# Laser_Array_Temp_High_BRD_V1_1sch.net
KiCad netlist of a schematic drawn in EAGLE
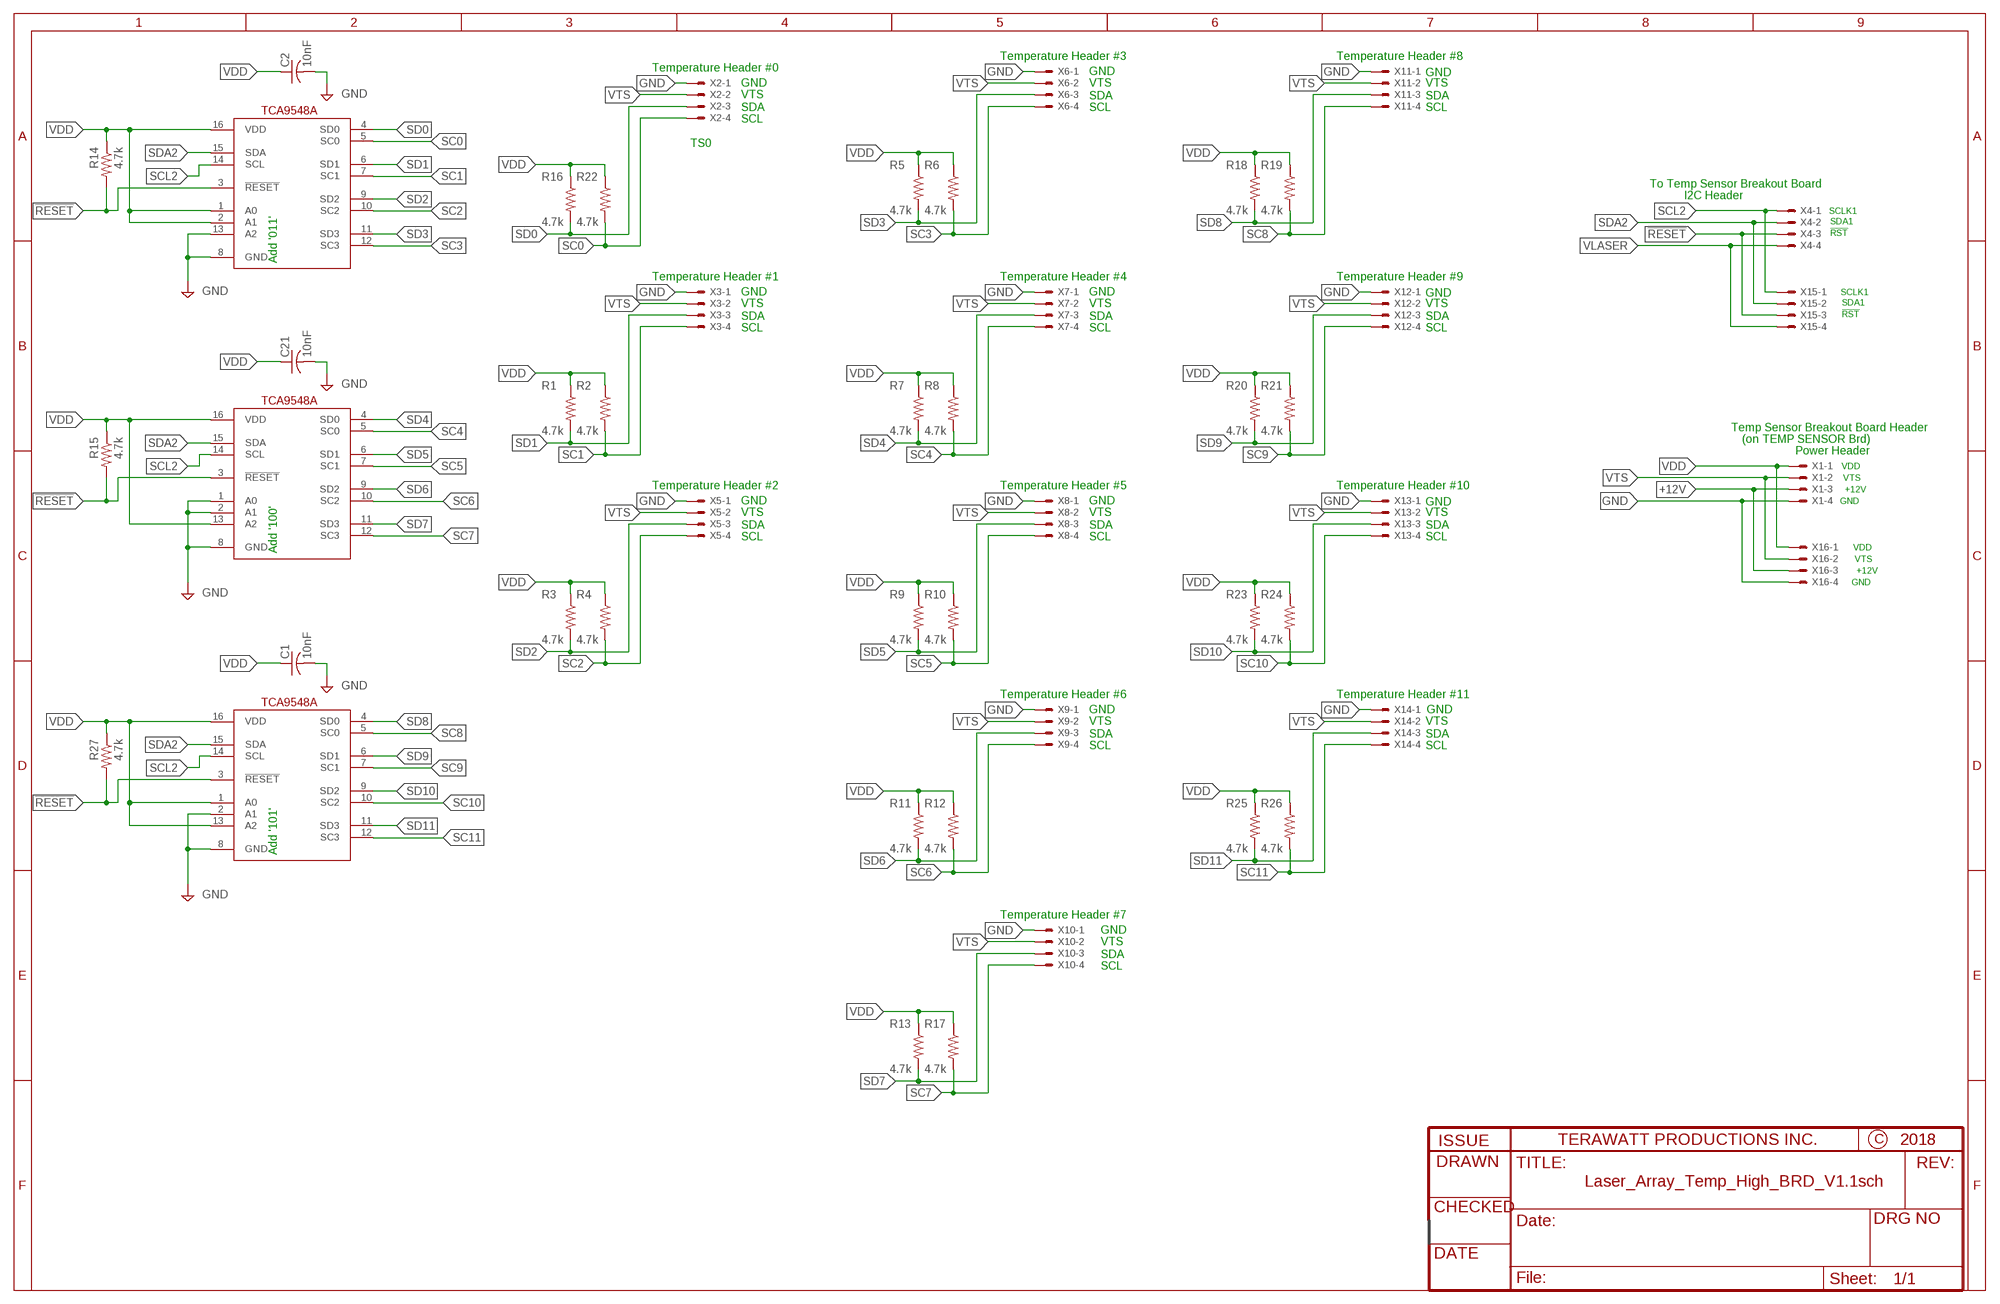
[diagram p0: schematic, sheet 1]

(export (version "E")
  (design (tool "Eeschema 10.0.6"))
  (components
    (comp (ref "C1")
      (value "10nF")
      (footprint "eagle-import:C0805")
      (libsource (lib "eagle-import") (part "C-USC0805"))
    )
    (comp (ref "C2")
      (value "10nF")
      (footprint "eagle-import:C0805")
      (libsource (lib "eagle-import") (part "C-USC0805"))
    )
    (comp (ref "C21")
      (value "10nF")
      (footprint "eagle-import:C0805")
      (libsource (lib "eagle-import") (part "C-USC0805"))
    )
    (comp (ref "R1")
      (value "4.7k")
      (footprint "eagle-import:M0805")
      (libsource (lib "eagle-import") (part "R-US_M0805"))
    )
    (comp (ref "R2")
      (value "4.7k")
      (footprint "eagle-import:M0805")
      (libsource (lib "eagle-import") (part "R-US_M0805"))
    )
    (comp (ref "R3")
      (value "4.7k")
      (footprint "eagle-import:M0805")
      (libsource (lib "eagle-import") (part "R-US_M0805"))
    )
    (comp (ref "R4")
      (value "4.7k")
      (footprint "eagle-import:M0805")
      (libsource (lib "eagle-import") (part "R-US_M0805"))
    )
    (comp (ref "R5")
      (value "4.7k")
      (footprint "eagle-import:M0805")
      (libsource (lib "eagle-import") (part "R-US_M0805"))
    )
    (comp (ref "R6")
      (value "4.7k")
      (footprint "eagle-import:M0805")
      (libsource (lib "eagle-import") (part "R-US_M0805"))
    )
    (comp (ref "R7")
      (value "4.7k")
      (footprint "eagle-import:M0805")
      (libsource (lib "eagle-import") (part "R-US_M0805"))
    )
    (comp (ref "R8")
      (value "4.7k")
      (footprint "eagle-import:M0805")
      (libsource (lib "eagle-import") (part "R-US_M0805"))
    )
    (comp (ref "R9")
      (value "4.7k")
      (footprint "eagle-import:M0805")
      (libsource (lib "eagle-import") (part "R-US_M0805"))
    )
    (comp (ref "R10")
      (value "4.7k")
      (footprint "eagle-import:M0805")
      (libsource (lib "eagle-import") (part "R-US_M0805"))
    )
    (comp (ref "R11")
      (value "4.7k")
      (footprint "eagle-import:M0805")
      (libsource (lib "eagle-import") (part "R-US_M0805"))
    )
    (comp (ref "R12")
      (value "4.7k")
      (footprint "eagle-import:M0805")
      (libsource (lib "eagle-import") (part "R-US_M0805"))
    )
    (comp (ref "R13")
      (value "4.7k")
      (footprint "eagle-import:M0805")
      (libsource (lib "eagle-import") (part "R-US_M0805"))
    )
    (comp (ref "R14")
      (value "4.7k")
      (footprint "eagle-import:M0805")
      (libsource (lib "eagle-import") (part "R-US_M0805"))
    )
    (comp (ref "R15")
      (value "4.7k")
      (footprint "eagle-import:M0805")
      (libsource (lib "eagle-import") (part "R-US_M0805"))
    )
    (comp (ref "R16")
      (value "4.7k")
      (footprint "eagle-import:M0805")
      (libsource (lib "eagle-import") (part "R-US_M0805"))
    )
    (comp (ref "R17")
      (value "4.7k")
      (footprint "eagle-import:M0805")
      (libsource (lib "eagle-import") (part "R-US_M0805"))
    )
    (comp (ref "R18")
      (value "4.7k")
      (footprint "eagle-import:M0805")
      (libsource (lib "eagle-import") (part "R-US_M0805"))
    )
    (comp (ref "R19")
      (value "4.7k")
      (footprint "eagle-import:M0805")
      (libsource (lib "eagle-import") (part "R-US_M0805"))
    )
    (comp (ref "R20")
      (value "4.7k")
      (footprint "eagle-import:M0805")
      (libsource (lib "eagle-import") (part "R-US_M0805"))
    )
    (comp (ref "R21")
      (value "4.7k")
      (footprint "eagle-import:M0805")
      (libsource (lib "eagle-import") (part "R-US_M0805"))
    )
    (comp (ref "R22")
      (value "4.7k")
      (footprint "eagle-import:M0805")
      (libsource (lib "eagle-import") (part "R-US_M0805"))
    )
    (comp (ref "R23")
      (value "4.7k")
      (footprint "eagle-import:M0805")
      (libsource (lib "eagle-import") (part "R-US_M0805"))
    )
    (comp (ref "R24")
      (value "4.7k")
      (footprint "eagle-import:M0805")
      (libsource (lib "eagle-import") (part "R-US_M0805"))
    )
    (comp (ref "R25")
      (value "4.7k")
      (footprint "eagle-import:M0805")
      (libsource (lib "eagle-import") (part "R-US_M0805"))
    )
    (comp (ref "R26")
      (value "4.7k")
      (footprint "eagle-import:M0805")
      (libsource (lib "eagle-import") (part "R-US_M0805"))
    )
    (comp (ref "R27")
      (value "4.7k")
      (footprint "eagle-import:M0805")
      (libsource (lib "eagle-import") (part "R-US_M0805"))
    )
    (comp (ref "U1")
      (value "TCA9546A")
      (footprint "eagle-import:SOIC16N")
      (libsource (lib "eagle-import") (part "TCA9546A"))
    )
    (comp (ref "U2")
      (value "TCA9546A")
      (footprint "eagle-import:SOIC16N")
      (libsource (lib "eagle-import") (part "TCA9546A"))
    )
    (comp (ref "U3")
      (value "TCA9546A")
      (footprint "eagle-import:SOIC16N")
      (libsource (lib "eagle-import") (part "TCA9546A"))
    )
    (comp (ref "X1")
      (value "22-23-2041")
      (footprint "eagle-import:22-23-2041")
      (fields (field (name "MF") "MOLEX"))
      (libsource (lib "eagle-import") (part "22-23-2041"))
    )
    (comp (ref "X2")
      (value "22-23-2041")
      (footprint "eagle-import:22-23-2041")
      (fields (field (name "MF") "MOLEX"))
      (libsource (lib "eagle-import") (part "22-23-2041"))
    )
    (comp (ref "X3")
      (value "22-23-2041")
      (footprint "eagle-import:22-23-2041")
      (fields (field (name "MF") "MOLEX"))
      (libsource (lib "eagle-import") (part "22-23-2041"))
    )
    (comp (ref "X4")
      (value "22-23-2041")
      (footprint "eagle-import:22-23-2041")
      (fields (field (name "MF") "MOLEX"))
      (libsource (lib "eagle-import") (part "22-23-2041"))
    )
    (comp (ref "X5")
      (value "22-23-2041")
      (footprint "eagle-import:22-23-2041")
      (fields (field (name "MF") "MOLEX"))
      (libsource (lib "eagle-import") (part "22-23-2041"))
    )
    (comp (ref "X6")
      (value "22-23-2041")
      (footprint "eagle-import:22-23-2041")
      (fields (field (name "MF") "MOLEX"))
      (libsource (lib "eagle-import") (part "22-23-2041"))
    )
    (comp (ref "X7")
      (value "22-23-2041")
      (footprint "eagle-import:22-23-2041")
      (fields (field (name "MF") "MOLEX"))
      (libsource (lib "eagle-import") (part "22-23-2041"))
    )
    (comp (ref "X8")
      (value "22-23-2041")
      (footprint "eagle-import:22-23-2041")
      (fields (field (name "MF") "MOLEX"))
      (libsource (lib "eagle-import") (part "22-23-2041"))
    )
    (comp (ref "X9")
      (value "22-23-2041")
      (footprint "eagle-import:22-23-2041")
      (fields (field (name "MF") "MOLEX"))
      (libsource (lib "eagle-import") (part "22-23-2041"))
    )
    (comp (ref "X10")
      (value "22-23-2041")
      (footprint "eagle-import:22-23-2041")
      (fields (field (name "MF") "MOLEX"))
      (libsource (lib "eagle-import") (part "22-23-2041"))
    )
    (comp (ref "X11")
      (value "22-23-2041")
      (footprint "eagle-import:22-23-2041")
      (fields (field (name "MF") "MOLEX"))
      (libsource (lib "eagle-import") (part "22-23-2041"))
    )
    (comp (ref "X12")
      (value "22-23-2041")
      (footprint "eagle-import:22-23-2041")
      (fields (field (name "MF") "MOLEX"))
      (libsource (lib "eagle-import") (part "22-23-2041"))
    )
    (comp (ref "X13")
      (value "22-23-2041")
      (footprint "eagle-import:22-23-2041")
      (fields (field (name "MF") "MOLEX"))
      (libsource (lib "eagle-import") (part "22-23-2041"))
    )
    (comp (ref "X14")
      (value "22-23-2041")
      (footprint "eagle-import:22-23-2041")
      (fields (field (name "MF") "MOLEX"))
      (libsource (lib "eagle-import") (part "22-23-2041"))
    )
    (comp (ref "X15")
      (value "22-23-2041")
      (footprint "eagle-import:22-23-2041")
      (fields (field (name "MF") "MOLEX"))
      (libsource (lib "eagle-import") (part "22-23-2041"))
    )
    (comp (ref "X16")
      (value "22-23-2041")
      (footprint "eagle-import:22-23-2041")
      (fields (field (name "MF") "MOLEX"))
      (libsource (lib "eagle-import") (part "22-23-2041"))
    )
  )
  (nets
    (net (code "1") (name "+12V") (class "Default")
      (node (ref "X1") (pin "3") (pinfunction "S_3") (pintype "passive"))
      (node (ref "X16") (pin "3") (pinfunction "S_3") (pintype "passive"))
    )
    (net (code "2") (name "/~{RESET}") (class "Default")
      (node (ref "R14") (pin "2") (pinfunction "2_2") (pintype "passive"))
      (node (ref "R15") (pin "2") (pinfunction "2_2") (pintype "passive"))
      (node (ref "R27") (pin "2") (pinfunction "2_2") (pintype "passive"))
      (node (ref "U1") (pin "3") (pinfunction "~{RESET}_3") (pintype "bidirectional"))
      (node (ref "U2") (pin "3") (pinfunction "~{RESET}_3") (pintype "bidirectional"))
      (node (ref "U3") (pin "3") (pinfunction "~{RESET}_3") (pintype "bidirectional"))
      (node (ref "X15") (pin "3") (pinfunction "S_3") (pintype "passive"))
      (node (ref "X4") (pin "3") (pinfunction "S_3") (pintype "passive"))
    )
    (net (code "3") (name "GND") (class "Default")
      (node (ref "C1") (pin "2") (pinfunction "2_2") (pintype "passive"))
      (node (ref "C2") (pin "2") (pinfunction "2_2") (pintype "passive"))
      (node (ref "C21") (pin "2") (pinfunction "2_2") (pintype "passive"))
      (node (ref "U1") (pin "13") (pinfunction "A2_13") (pintype "bidirectional"))
      (node (ref "U1") (pin "8") (pinfunction "GND_8") (pintype "bidirectional"))
      (node (ref "U2") (pin "1") (pinfunction "A0_1") (pintype "bidirectional"))
      (node (ref "U2") (pin "2") (pinfunction "A1_2") (pintype "bidirectional"))
      (node (ref "U2") (pin "8") (pinfunction "GND_8") (pintype "bidirectional"))
      (node (ref "U3") (pin "2") (pinfunction "A1_2") (pintype "bidirectional"))
      (node (ref "U3") (pin "8") (pinfunction "GND_8") (pintype "bidirectional"))
      (node (ref "X1") (pin "4") (pinfunction "S_4") (pintype "passive"))
      (node (ref "X10") (pin "1") (pinfunction "S_1") (pintype "passive"))
      (node (ref "X11") (pin "1") (pinfunction "S_1") (pintype "passive"))
      (node (ref "X12") (pin "1") (pinfunction "S_1") (pintype "passive"))
      (node (ref "X13") (pin "1") (pinfunction "S_1") (pintype "passive"))
      (node (ref "X14") (pin "1") (pinfunction "S_1") (pintype "passive"))
      (node (ref "X16") (pin "4") (pinfunction "S_4") (pintype "passive"))
      (node (ref "X2") (pin "1") (pinfunction "S_1") (pintype "passive"))
      (node (ref "X3") (pin "1") (pinfunction "S_1") (pintype "passive"))
      (node (ref "X5") (pin "1") (pinfunction "S_1") (pintype "passive"))
      (node (ref "X6") (pin "1") (pinfunction "S_1") (pintype "passive"))
      (node (ref "X7") (pin "1") (pinfunction "S_1") (pintype "passive"))
      (node (ref "X8") (pin "1") (pinfunction "S_1") (pintype "passive"))
      (node (ref "X9") (pin "1") (pinfunction "S_1") (pintype "passive"))
    )
    (net (code "4") (name "SC0") (class "Default")
      (node (ref "R22") (pin "2") (pinfunction "2_2") (pintype "passive"))
      (node (ref "U1") (pin "5") (pinfunction "SC0_5") (pintype "bidirectional"))
      (node (ref "X2") (pin "4") (pinfunction "S_4") (pintype "passive"))
    )
    (net (code "5") (name "SC1") (class "Default")
      (node (ref "R2") (pin "2") (pinfunction "2_2") (pintype "passive"))
      (node (ref "U1") (pin "7") (pinfunction "SC1_7") (pintype "bidirectional"))
      (node (ref "X3") (pin "4") (pinfunction "S_4") (pintype "passive"))
    )
    (net (code "6") (name "SC2") (class "Default")
      (node (ref "R4") (pin "2") (pinfunction "2_2") (pintype "passive"))
      (node (ref "U1") (pin "10") (pinfunction "SC2_10") (pintype "bidirectional"))
      (node (ref "X5") (pin "4") (pinfunction "S_4") (pintype "passive"))
    )
    (net (code "7") (name "SC3") (class "Default")
      (node (ref "R6") (pin "2") (pinfunction "2_2") (pintype "passive"))
      (node (ref "U1") (pin "12") (pinfunction "SC3_12") (pintype "bidirectional"))
      (node (ref "X6") (pin "4") (pinfunction "S_4") (pintype "passive"))
    )
    (net (code "8") (name "SC4") (class "Default")
      (node (ref "R8") (pin "2") (pinfunction "2_2") (pintype "passive"))
      (node (ref "U2") (pin "5") (pinfunction "SC0_5") (pintype "bidirectional"))
      (node (ref "X7") (pin "4") (pinfunction "S_4") (pintype "passive"))
    )
    (net (code "9") (name "SC5") (class "Default")
      (node (ref "R10") (pin "2") (pinfunction "2_2") (pintype "passive"))
      (node (ref "U2") (pin "7") (pinfunction "SC1_7") (pintype "bidirectional"))
      (node (ref "X8") (pin "4") (pinfunction "S_4") (pintype "passive"))
    )
    (net (code "10") (name "SC6") (class "Default")
      (node (ref "R12") (pin "2") (pinfunction "2_2") (pintype "passive"))
      (node (ref "U2") (pin "10") (pinfunction "SC2_10") (pintype "bidirectional"))
      (node (ref "X9") (pin "4") (pinfunction "S_4") (pintype "passive"))
    )
    (net (code "11") (name "SC7") (class "Default")
      (node (ref "R17") (pin "2") (pinfunction "2_2") (pintype "passive"))
      (node (ref "U2") (pin "12") (pinfunction "SC3_12") (pintype "bidirectional"))
      (node (ref "X10") (pin "4") (pinfunction "S_4") (pintype "passive"))
    )
    (net (code "12") (name "SC8") (class "Default")
      (node (ref "R19") (pin "2") (pinfunction "2_2") (pintype "passive"))
      (node (ref "U3") (pin "5") (pinfunction "SC0_5") (pintype "bidirectional"))
      (node (ref "X11") (pin "4") (pinfunction "S_4") (pintype "passive"))
    )
    (net (code "13") (name "SC9") (class "Default")
      (node (ref "R21") (pin "2") (pinfunction "2_2") (pintype "passive"))
      (node (ref "U3") (pin "7") (pinfunction "SC1_7") (pintype "bidirectional"))
      (node (ref "X12") (pin "4") (pinfunction "S_4") (pintype "passive"))
    )
    (net (code "14") (name "SC10") (class "Default")
      (node (ref "R24") (pin "2") (pinfunction "2_2") (pintype "passive"))
      (node (ref "U3") (pin "10") (pinfunction "SC2_10") (pintype "bidirectional"))
      (node (ref "X13") (pin "4") (pinfunction "S_4") (pintype "passive"))
    )
    (net (code "15") (name "SC11") (class "Default")
      (node (ref "R26") (pin "2") (pinfunction "2_2") (pintype "passive"))
      (node (ref "U3") (pin "12") (pinfunction "SC3_12") (pintype "bidirectional"))
      (node (ref "X14") (pin "4") (pinfunction "S_4") (pintype "passive"))
    )
    (net (code "16") (name "SCL2") (class "Default")
      (node (ref "U1") (pin "14") (pinfunction "SCL_14") (pintype "bidirectional"))
      (node (ref "U2") (pin "14") (pinfunction "SCL_14") (pintype "bidirectional"))
      (node (ref "U3") (pin "14") (pinfunction "SCL_14") (pintype "bidirectional"))
      (node (ref "X15") (pin "1") (pinfunction "S_1") (pintype "passive"))
      (node (ref "X4") (pin "1") (pinfunction "S_1") (pintype "passive"))
    )
    (net (code "17") (name "SD0") (class "Default")
      (node (ref "R16") (pin "2") (pinfunction "2_2") (pintype "passive"))
      (node (ref "U1") (pin "4") (pinfunction "SD0_4") (pintype "bidirectional"))
      (node (ref "X2") (pin "3") (pinfunction "S_3") (pintype "passive"))
    )
    (net (code "18") (name "SD1") (class "Default")
      (node (ref "R1") (pin "2") (pinfunction "2_2") (pintype "passive"))
      (node (ref "U1") (pin "6") (pinfunction "SD1_6") (pintype "bidirectional"))
      (node (ref "X3") (pin "3") (pinfunction "S_3") (pintype "passive"))
    )
    (net (code "19") (name "SD2") (class "Default")
      (node (ref "R3") (pin "2") (pinfunction "2_2") (pintype "passive"))
      (node (ref "U1") (pin "9") (pinfunction "SD2_9") (pintype "bidirectional"))
      (node (ref "X5") (pin "3") (pinfunction "S_3") (pintype "passive"))
    )
    (net (code "20") (name "SD3") (class "Default")
      (node (ref "R5") (pin "2") (pinfunction "2_2") (pintype "passive"))
      (node (ref "U1") (pin "11") (pinfunction "SD3_11") (pintype "bidirectional"))
      (node (ref "X6") (pin "3") (pinfunction "S_3") (pintype "passive"))
    )
    (net (code "21") (name "SD4") (class "Default")
      (node (ref "R7") (pin "2") (pinfunction "2_2") (pintype "passive"))
      (node (ref "U2") (pin "4") (pinfunction "SD0_4") (pintype "bidirectional"))
      (node (ref "X7") (pin "3") (pinfunction "S_3") (pintype "passive"))
    )
    (net (code "22") (name "SD5") (class "Default")
      (node (ref "R9") (pin "2") (pinfunction "2_2") (pintype "passive"))
      (node (ref "U2") (pin "6") (pinfunction "SD1_6") (pintype "bidirectional"))
      (node (ref "X8") (pin "3") (pinfunction "S_3") (pintype "passive"))
    )
    (net (code "23") (name "SD6") (class "Default")
      (node (ref "R11") (pin "2") (pinfunction "2_2") (pintype "passive"))
      (node (ref "U2") (pin "9") (pinfunction "SD2_9") (pintype "bidirectional"))
      (node (ref "X9") (pin "3") (pinfunction "S_3") (pintype "passive"))
    )
    (net (code "24") (name "SD7") (class "Default")
      (node (ref "R13") (pin "2") (pinfunction "2_2") (pintype "passive"))
      (node (ref "U2") (pin "11") (pinfunction "SD3_11") (pintype "bidirectional"))
      (node (ref "X10") (pin "3") (pinfunction "S_3") (pintype "passive"))
    )
    (net (code "25") (name "SD8") (class "Default")
      (node (ref "R18") (pin "2") (pinfunction "2_2") (pintype "passive"))
      (node (ref "U3") (pin "4") (pinfunction "SD0_4") (pintype "bidirectional"))
      (node (ref "X11") (pin "3") (pinfunction "S_3") (pintype "passive"))
    )
    (net (code "26") (name "SD9") (class "Default")
      (node (ref "R20") (pin "2") (pinfunction "2_2") (pintype "passive"))
      (node (ref "U3") (pin "6") (pinfunction "SD1_6") (pintype "bidirectional"))
      (node (ref "X12") (pin "3") (pinfunction "S_3") (pintype "passive"))
    )
    (net (code "27") (name "SD10") (class "Default")
      (node (ref "R23") (pin "2") (pinfunction "2_2") (pintype "passive"))
      (node (ref "U3") (pin "9") (pinfunction "SD2_9") (pintype "bidirectional"))
      (node (ref "X13") (pin "3") (pinfunction "S_3") (pintype "passive"))
    )
    (net (code "28") (name "SD11") (class "Default")
      (node (ref "R25") (pin "2") (pinfunction "2_2") (pintype "passive"))
      (node (ref "U3") (pin "11") (pinfunction "SD3_11") (pintype "bidirectional"))
      (node (ref "X14") (pin "3") (pinfunction "S_3") (pintype "passive"))
    )
    (net (code "29") (name "SDA2") (class "Default")
      (node (ref "U1") (pin "15") (pinfunction "SDA_15") (pintype "bidirectional"))
      (node (ref "U2") (pin "15") (pinfunction "SDA_15") (pintype "bidirectional"))
      (node (ref "U3") (pin "15") (pinfunction "SDA_15") (pintype "bidirectional"))
      (node (ref "X15") (pin "2") (pinfunction "S_2") (pintype "passive"))
      (node (ref "X4") (pin "2") (pinfunction "S_2") (pintype "passive"))
    )
    (net (code "30") (name "VDD") (class "Default")
      (node (ref "C1") (pin "1") (pinfunction "1_1") (pintype "passive"))
      (node (ref "C2") (pin "1") (pinfunction "1_1") (pintype "passive"))
      (node (ref "C21") (pin "1") (pinfunction "1_1") (pintype "passive"))
      (node (ref "R1") (pin "1") (pinfunction "1_1") (pintype "passive"))
      (node (ref "R10") (pin "1") (pinfunction "1_1") (pintype "passive"))
      (node (ref "R11") (pin "1") (pinfunction "1_1") (pintype "passive"))
      (node (ref "R12") (pin "1") (pinfunction "1_1") (pintype "passive"))
      (node (ref "R13") (pin "1") (pinfunction "1_1") (pintype "passive"))
      (node (ref "R14") (pin "1") (pinfunction "1_1") (pintype "passive"))
      (node (ref "R15") (pin "1") (pinfunction "1_1") (pintype "passive"))
      (node (ref "R16") (pin "1") (pinfunction "1_1") (pintype "passive"))
      (node (ref "R17") (pin "1") (pinfunction "1_1") (pintype "passive"))
      (node (ref "R18") (pin "1") (pinfunction "1_1") (pintype "passive"))
      (node (ref "R19") (pin "1") (pinfunction "1_1") (pintype "passive"))
      (node (ref "R2") (pin "1") (pinfunction "1_1") (pintype "passive"))
      (node (ref "R20") (pin "1") (pinfunction "1_1") (pintype "passive"))
      (node (ref "R21") (pin "1") (pinfunction "1_1") (pintype "passive"))
      (node (ref "R22") (pin "1") (pinfunction "1_1") (pintype "passive"))
      (node (ref "R23") (pin "1") (pinfunction "1_1") (pintype "passive"))
      (node (ref "R24") (pin "1") (pinfunction "1_1") (pintype "passive"))
      (node (ref "R25") (pin "1") (pinfunction "1_1") (pintype "passive"))
      (node (ref "R26") (pin "1") (pinfunction "1_1") (pintype "passive"))
      (node (ref "R27") (pin "1") (pinfunction "1_1") (pintype "passive"))
      (node (ref "R3") (pin "1") (pinfunction "1_1") (pintype "passive"))
      (node (ref "R4") (pin "1") (pinfunction "1_1") (pintype "passive"))
      (node (ref "R5") (pin "1") (pinfunction "1_1") (pintype "passive"))
      (node (ref "R6") (pin "1") (pinfunction "1_1") (pintype "passive"))
      (node (ref "R7") (pin "1") (pinfunction "1_1") (pintype "passive"))
      (node (ref "R8") (pin "1") (pinfunction "1_1") (pintype "passive"))
      (node (ref "R9") (pin "1") (pinfunction "1_1") (pintype "passive"))
      (node (ref "U1") (pin "1") (pinfunction "A0_1") (pintype "bidirectional"))
      (node (ref "U1") (pin "16") (pinfunction "VDD_16") (pintype "bidirectional"))
      (node (ref "U1") (pin "2") (pinfunction "A1_2") (pintype "bidirectional"))
      (node (ref "U2") (pin "13") (pinfunction "A2_13") (pintype "bidirectional"))
      (node (ref "U2") (pin "16") (pinfunction "VDD_16") (pintype "bidirectional"))
      (node (ref "U3") (pin "1") (pinfunction "A0_1") (pintype "bidirectional"))
      (node (ref "U3") (pin "13") (pinfunction "A2_13") (pintype "bidirectional"))
      (node (ref "U3") (pin "16") (pinfunction "VDD_16") (pintype "bidirectional"))
      (node (ref "X1") (pin "1") (pinfunction "S_1") (pintype "passive"))
      (node (ref "X16") (pin "1") (pinfunction "S_1") (pintype "passive"))
    )
    (net (code "31") (name "VLASER") (class "Default")
      (node (ref "X15") (pin "4") (pinfunction "S_4") (pintype "passive"))
      (node (ref "X4") (pin "4") (pinfunction "S_4") (pintype "passive"))
    )
    (net (code "32") (name "VTS") (class "Default")
      (node (ref "X1") (pin "2") (pinfunction "S_2") (pintype "passive"))
      (node (ref "X10") (pin "2") (pinfunction "S_2") (pintype "passive"))
      (node (ref "X11") (pin "2") (pinfunction "S_2") (pintype "passive"))
      (node (ref "X12") (pin "2") (pinfunction "S_2") (pintype "passive"))
      (node (ref "X13") (pin "2") (pinfunction "S_2") (pintype "passive"))
      (node (ref "X14") (pin "2") (pinfunction "S_2") (pintype "passive"))
      (node (ref "X16") (pin "2") (pinfunction "S_2") (pintype "passive"))
      (node (ref "X2") (pin "2") (pinfunction "S_2") (pintype "passive"))
      (node (ref "X3") (pin "2") (pinfunction "S_2") (pintype "passive"))
      (node (ref "X5") (pin "2") (pinfunction "S_2") (pintype "passive"))
      (node (ref "X6") (pin "2") (pinfunction "S_2") (pintype "passive"))
      (node (ref "X7") (pin "2") (pinfunction "S_2") (pintype "passive"))
      (node (ref "X8") (pin "2") (pinfunction "S_2") (pintype "passive"))
      (node (ref "X9") (pin "2") (pinfunction "S_2") (pintype "passive"))
    )
  )
)
